# ELoad_Control_Assembly_Gen_2_-_PSU.net
KiCad netlist of a schematic drawn in Altium Designer
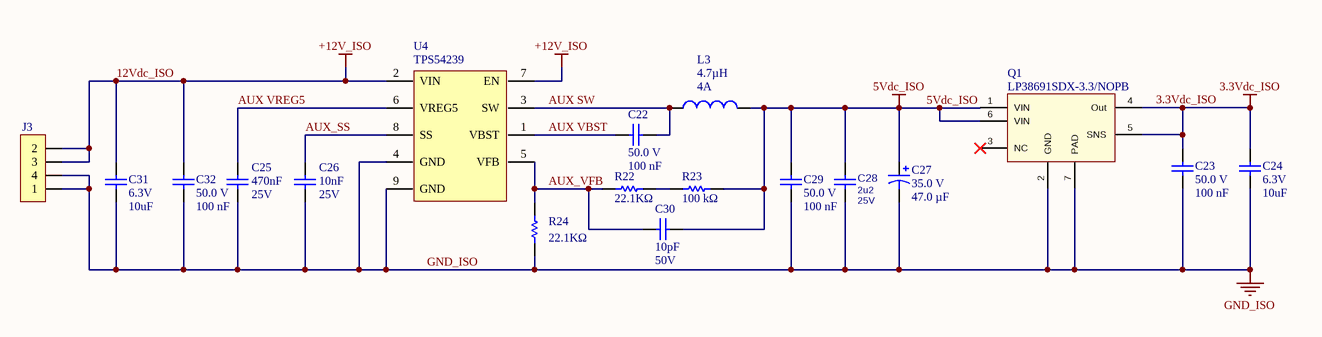
[diagram p0: ELoad Control Assembly Gen 2 - PSU.SchDoc]

(export (version "E")
  (design (tool "Eeschema 10.0.6"))
  (components
    (comp (ref "C22")
      (value "Cap")
      (footprint "Cap,0805")
      (description "Capacitor; Ceramic; Cap 0.1 uF; Tol 5%; Vol-Rtg 50 VDC; SMT; 0805; X7R; Tape & Reel")
      (fields
        (field (name "MANUFACTURER PART NUMBER") "08055C104JAT2A")
        (field (name "VOLTAGE RATING (DC)") "50.0 V")
        (field (name "CAPACITANCE") "100 nF")
      )
      (libsource (lib "Master SEPT2019") (part "Cap,0805,100nf,50V,5%,08055C104JAT2A"))
    )
    (comp (ref "C23")
      (value "Cap")
      (footprint "Cap,0805")
      (description "Capacitor; Ceramic; Cap 0.1 uF; Tol 5%; Vol-Rtg 50 VDC; SMT; 0805; X7R; Tape & Reel")
      (fields
        (field (name "MANUFACTURER PART NUMBER") "08055C104JAT2A")
        (field (name "VOLTAGE RATING (DC)") "50.0 V")
        (field (name "CAPACITANCE") "100 nF")
      )
      (libsource (lib "Master SEPT2019") (part "Cap,0805,100nf,50V,5%,08055C104JAT2A"))
    )
    (comp (ref "C24")
      (value "Cap")
      (footprint "Cap,0805")
      (description "CL21 Series 10 uF 6.3V ±10 % Tolerance X5R SMT Multilayer Ceramic Capacitor")
      (fields
        (field (name "TOLERANCE") "±10%")
        (field (name "VOLTAGE - RATED") "6.3V")
        (field (name "CAPACITANCE") "10uF")
      )
      (libsource (lib "Master SEPT2019") (part "Cap,0805,10uf,6.3V,10%,CL21A106KQFNNNG"))
    )
    (comp (ref "C25")
      (value "Cap")
      (footprint "Cap,0805")
      (description "0.47µF ±10% 25V Ceramic Capacitor X7R 0805 (2012 Metric)")
      (fields
        (field (name "MANUFACTURER") "TDK Corporation")
        (field (name "VOLTAGE RATING (DC)") "25V")
        (field (name "CAPACITANCE") "470nF")
      )
      (libsource (lib "Master SEPT2019") (part "Cap,0805,470nf,25V,10%,CGA4J2X7R1E474K125AA"))
    )
    (comp (ref "C26")
      (value "Cap")
      (footprint "Cap,0805")
      (description "CAP CER 10000PF 25V X7R 0805")
      (fields
        (field (name "MANUFACTURER") "Samsung Electro-Mechanics")
        (field (name "VOLTAGE RATING (DC)") "25V")
        (field (name "CAPACITANCE") "10nF")
      )
      (libsource (lib "Master SEPT2019") (part "Cap,0805,10nF,±10%,25Vdc"))
    )
    (comp (ref "C27")
      (value "Nichicon UCW1V470MCL1GS")
      (footprint "Cap, SMD, polerized, 5mm spacing")
      (description "47uF 35 V dc Aluminium Electrolytic Capacitor, CW Series 7000h 6.3(Dia.)x8.7mm")
      (fields
        (field (name "MANUFACTURER PART NUMBER") "UCW1V470MCL1GS")
        (field (name "VOLTAGE RATING (DC)") "35.0 V")
        (field (name "CAPACITANCE") "47.0 µF")
      )
      (libsource (lib "Master SEPT2019") (part "Cap, Polar,SMD, 47uF,35V,UCW1V470MCL1GS"))
    )
    (comp (ref "C28")
      (value "2u2")
      (footprint "res, 0805, HD")
      (description "Cap,SMD,MLCC,2.2uF 25V X7R 10%,0805")
      (fields (field (name "MANUFACTURER") "Murata") (field (name "VOLTAGE") "25V"))
      (libsource (lib "Master SEPT_2019") (part "Cap,0805,2.2uF,10%,25V"))
    )
    (comp (ref "C29")
      (value "Cap")
      (footprint "Cap,0805")
      (description "Capacitor; Ceramic; Cap 0.1 uF; Tol 5%; Vol-Rtg 50 VDC; SMT; 0805; X7R; Tape & Reel")
      (fields
        (field (name "MANUFACTURER PART NUMBER") "08055C104JAT2A")
        (field (name "VOLTAGE RATING (DC)") "50.0 V")
        (field (name "CAPACITANCE") "100 nF")
      )
      (libsource (lib "Master SEPT_2019") (part "Cap,0805,100nf,50V,5%,08055C104JAT2A"))
    )
    (comp (ref "C30")
      (value "CL21C100JBANNNC")
      (footprint "CAP, 0805, HD")
      (description "CAP CER 10PF 50V C0G/NP0 0805")
      (fields
        (field (name "MANUFACTURER") "Samsung Electro-Mechanics")
        (field (name "TOLERANCE") "±5%")
        (field (name "CAPACITANCE") "10pF")
        (field (name "VOLTAGE - RATED") "50V")
      )
      (libsource (lib "Master SEPT_2019") (part "Cap,0805,10pf,±5%,C0G, NP0,CL21C100JBANNNC"))
    )
    (comp (ref "C31")
      (value "Cap")
      (footprint "Cap,0805")
      (description "CL21 Series 10 uF 6.3V ±10 % Tolerance X5R SMT Multilayer Ceramic Capacitor")
      (fields
        (field (name "TOLERANCE") "±10%")
        (field (name "VOLTAGE - RATED") "6.3V")
        (field (name "CAPACITANCE") "10uF")
      )
      (libsource (lib "Master SEPT2019") (part "Cap,0805,10uf,6.3V,10%,CL21A106KQFNNNG"))
    )
    (comp (ref "C32")
      (value "Cap")
      (footprint "Cap,0805")
      (description "Capacitor; Ceramic; Cap 0.1 uF; Tol 5%; Vol-Rtg 50 VDC; SMT; 0805; X7R; Tape & Reel")
      (fields
        (field (name "MANUFACTURER PART NUMBER") "08055C104JAT2A")
        (field (name "VOLTAGE RATING (DC)") "50.0 V")
        (field (name "CAPACITANCE") "100 nF")
      )
      (libsource (lib "Master SEPT2019") (part "Cap,0805,100nf,50V,5%,08055C104JAT2A"))
    )
    (comp (ref "J3")
      (value "0022112042")
      (footprint "conn, molex, 0.1\", 4 pin")
      (description "Connector Header Through Hole 4 position 0.100\" (2.54mm)")
      (fields (field (name "MANUFACTURER") "Molex"))
      (libsource (lib "Master JULY2019") (part "Connector,Through Hole,Molex,2.54mm,4Pin,Vert"))
    )
    (comp (ref "L3")
      (value "1255AY-4R7M=P3")
      (footprint "Ind,Non-Stand,Murata,1255AY")
      (description "FIXED IND 4.7UH 4.5A 27.6 MOHM")
      (fields
        (field (name "MANUFACTURER") "Murata Electronics North America")
        (field (name "TOLERANCE") "±20%")
        (field (name "INDUCTANCE") "4.7µH")
        (field (name "CURRENT RATING (AMPS)") "4A")
      )
      (libsource (lib "Master SEPT_2019") (part "IND,NON-Stand,SMD,4.7uH,4.5A,27.6mOhm,1255AY-4R7M=P3"))
    )
    (comp (ref "Q1")
      (value "LP38691SDX-3.3/NOPB")
      (footprint "6-WSON (3x3)")
      (description "IC REG LIN POS ADJ 500MA 6WSON")
      (fields
        (field (name "MFG P/N") "LP38691SDX-3.3/NOPB")
        (field (name "MANUFACTURER") "Texas Instruments")
        (field (name "BASE PART NUMBER") "LP38691")
      )
      (libsource (lib "Master SEPT2019") (part "Reg,Linear,Fixed,500mA,10Vin_Max,3.3Vdc,LP38691SD-ADJ/NOPB"))
    )
    (comp (ref "R22")
      (value "RC0805FR-0722K1L")
      (footprint "res, 0805, HD")
      (description "22.1 kOhms ±1% 0.125W, 1/8W Chip Resistor 0805 (2012 Metric) Moisture Resistant Thick Film")
      (fields (field (name "RESISTANCE") "22.1KΩ"))
      (libsource (lib "Master SEPT_2019") (part "Res,0805,22.1K,1%,100ppm,RC0805FR-0722K1L"))
    )
    (comp (ref "R23")
      (value "Res,0805,100kΩ,1%,100ppm,CRCW0805100KFKEA")
      (footprint "res, 0805, HD")
      (description "100 kOhms ±1% 0.125W, 1/8W Chip Resistor 0805 (2012 Metric) Thick Film")
      (fields
        (field (name "MANUFACTURER PART NUMBER") "CRCW0805100KFKEA")
        (field (name "MANUFACTURER") "Vishay")
        (field (name "RESISTANCE") "100 kΩ")
      )
      (libsource (lib "Master SEPT2019") (part "Res,0805,100kΩ,1%,100ppm,CRCW0805100KFKEA"))
    )
    (comp (ref "R24")
      (value "RC0805FR-0722K1L")
      (footprint "res, 0805, HD")
      (description "22.1 kOhms ±1% 0.125W, 1/8W Chip Resistor 0805 (2012 Metric) Moisture Resistant Thick Film")
      (fields (field (name "RESISTANCE") "22.1KΩ"))
      (libsource (lib "Master SEPT_2019") (part "Res,0805,22.1K,1%,100ppm,RC0805FR-0722K1L"))
    )
    (comp (ref "U4")
      (value "TPS54239")
      (footprint "SOIC-8 PowerPad(pin4)")
      (libsource (lib "Master SEPT_2019") (part "Reg, Switching, Buck,23-4.5Vdcin,2A,TPS54239EDDAR"))
    )
  )
  (nets
    (net (code "1") (name "+12V_ISO") (class "Default")
      (node (ref "C31") (pin "2") (pinfunction "2_2") (pintype "passive"))
      (node (ref "C32") (pin "2") (pinfunction "2_2") (pintype "passive"))
      (node (ref "J3") (pin "2") (pinfunction "2_2") (pintype "passive"))
      (node (ref "J3") (pin "3") (pinfunction "3_3") (pintype "passive"))
      (node (ref "U4") (pin "2") (pinfunction "VIN_2") (pintype "passive"))
      (node (ref "U4") (pin "7") (pinfunction "EN_7") (pintype "passive"))
    )
    (net (code "2") (name "/AUX SW") (class "Default")
      (node (ref "C22") (pin "1") (pinfunction "1_1") (pintype "passive"))
      (node (ref "L3") (pin "1") (pinfunction "1_1") (pintype "passive"))
      (node (ref "U4") (pin "3") (pinfunction "SW_3") (pintype "passive"))
    )
    (net (code "3") (name "/AUX VBST") (class "Default")
      (node (ref "C22") (pin "2") (pinfunction "2_2") (pintype "passive"))
      (node (ref "U4") (pin "1") (pinfunction "VBST_1") (pintype "passive"))
    )
    (net (code "4") (name "/AUX VREG5") (class "Default")
      (node (ref "C25") (pin "2") (pinfunction "2_2") (pintype "passive"))
      (node (ref "U4") (pin "6") (pinfunction "VREG5_6") (pintype "passive"))
    )
    (net (code "5") (name "/AUX_SS") (class "Default")
      (node (ref "C26") (pin "2") (pinfunction "2_2") (pintype "passive"))
      (node (ref "U4") (pin "8") (pinfunction "SS_8") (pintype "passive"))
    )
    (net (code "6") (name "/AUX_VFB") (class "Default")
      (node (ref "C30") (pin "2") (pinfunction "2_2") (pintype "passive"))
      (node (ref "R22") (pin "1") (pinfunction "1_1") (pintype "passive"))
      (node (ref "R24") (pin "2") (pinfunction "2_2") (pintype "passive"))
      (node (ref "U4") (pin "5") (pinfunction "VFB_5") (pintype "passive"))
    )
    (net (code "7") (name "3.3Vdc_ISO") (class "Default")
      (node (ref "C23") (pin "2") (pinfunction "2_2") (pintype "passive"))
      (node (ref "C24") (pin "2") (pinfunction "2_2") (pintype "passive"))
      (node (ref "Q1") (pin "4") (pinfunction "Out_4") (pintype "power_in"))
      (node (ref "Q1") (pin "5") (pinfunction "SNS_5") (pintype "passive"))
    )
    (net (code "8") (name "5Vdc_ISO") (class "Default")
      (node (ref "C27") (pin "1") (pinfunction "1_1") (pintype "passive"))
      (node (ref "C28") (pin "2") (pintype "passive"))
      (node (ref "C29") (pin "2") (pinfunction "2_2") (pintype "passive"))
      (node (ref "C30") (pin "1") (pinfunction "1_1") (pintype "passive"))
      (node (ref "L3") (pin "2") (pinfunction "2_2") (pintype "passive"))
      (node (ref "Q1") (pin "1") (pinfunction "VIN_1") (pintype "power_in"))
      (node (ref "Q1") (pin "6") (pinfunction "VIN_6") (pintype "power_in"))
      (node (ref "R23") (pin "1") (pinfunction "1_1") (pintype "passive"))
    )
    (net (code "9") (name "GND_ISO") (class "Default")
      (node (ref "C23") (pin "1") (pinfunction "1_1") (pintype "passive"))
      (node (ref "C24") (pin "1") (pinfunction "1_1") (pintype "passive"))
      (node (ref "C25") (pin "1") (pinfunction "1_1") (pintype "passive"))
      (node (ref "C26") (pin "1") (pinfunction "1_1") (pintype "passive"))
      (node (ref "C27") (pin "2") (pinfunction "2_2") (pintype "passive"))
      (node (ref "C28") (pin "1") (pintype "passive"))
      (node (ref "C29") (pin "1") (pinfunction "1_1") (pintype "passive"))
      (node (ref "C31") (pin "1") (pinfunction "1_1") (pintype "passive"))
      (node (ref "C32") (pin "1") (pinfunction "1_1") (pintype "passive"))
      (node (ref "J3") (pin "1") (pinfunction "1_1") (pintype "passive"))
      (node (ref "J3") (pin "4") (pinfunction "4_4") (pintype "passive"))
      (node (ref "Q1") (pin "2") (pinfunction "GND_2") (pintype "power_in"))
      (node (ref "Q1") (pin "7") (pinfunction "PAD_7") (pintype "power_in"))
      (node (ref "R24") (pin "1") (pinfunction "1_1") (pintype "passive"))
      (node (ref "U4") (pin "4") (pinfunction "GND_4") (pintype "passive"))
      (node (ref "U4") (pin "9") (pinfunction "GND_9") (pintype "passive"))
    )
    (net (code "10") (name "Net-(R22-Pad2)") (class "Default")
      (node (ref "R22") (pin "2") (pinfunction "2_2") (pintype "passive"))
      (node (ref "R23") (pin "2") (pinfunction "2_2") (pintype "passive"))
    )
    (net (code "11") (name "unconnected-(Q1-NC-Pad3)") (class "Default")
      (node (ref "Q1") (pin "3") (pinfunction "NC_3") (pintype "passive+no_connect"))
    )
  )
)
